# 2switch_LED_series.net
KiCad netlist of a schematic drawn in EAGLE
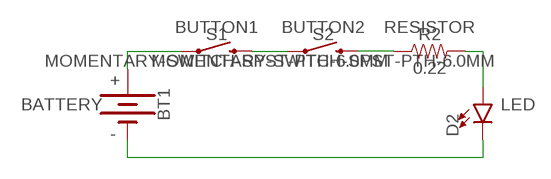
[diagram p0: schematic, sheet 1]

(export (version "E")
  (design (tool "Eeschema 10.0.6"))
  (components
    (comp (ref "BT1")
      (value "BATTERY-9V")
      (footprint "eagle-import:BATTCON_9V")
      (libsource (lib "eagle-import") (part "BATTERY-9V"))
    )
    (comp (ref "D2")
      (value "LED5MM")
      (footprint "eagle-import:LED_5MM")
      (libsource (lib "eagle-import") (part "LED5MM"))
    )
    (comp (ref "R2")
      (value "0.22")
      (footprint "eagle-import:0805")
      (libsource (lib "eagle-import") (part "0.22OHM-0805-1/4W-1%"))
    )
    (comp (ref "S1")
      (value "MOMENTARY-SWITCH-SPST-PTH-6.0MM")
      (footprint "eagle-import:TACTILE_SWITCH_PTH_6.0MM")
      (libsource (lib "eagle-import") (part "MOMENTARY-SWITCH-SPST-PTH-6.0MM"))
    )
    (comp (ref "S2")
      (value "MOMENTARY-SWITCH-SPST-PTH-6.0MM")
      (footprint "eagle-import:TACTILE_SWITCH_PTH_6.0MM")
      (libsource (lib "eagle-import") (part "MOMENTARY-SWITCH-SPST-PTH-6.0MM"))
    )
  )
  (nets
    (net (code "1") (name "Net-(BT1-Pad+)") (class "Default")
      (node (ref "BT1") (pin "+") (pinfunction "+_+") (pintype "power_in"))
      (node (ref "S1") (pin "1") (pinfunction "1_1") (pintype "passive"))
    )
    (net (code "2") (name "Net-(D2-C)") (class "Default")
      (node (ref "BT1") (pin "-") (pinfunction "-_-") (pintype "power_in"))
      (node (ref "D2") (pin "K") (pinfunction "C_K") (pintype "passive"))
    )
    (net (code "3") (name "Net-(D2-PadA)") (class "Default")
      (node (ref "D2") (pin "A") (pinfunction "A_A") (pintype "passive"))
      (node (ref "R2") (pin "2") (pinfunction "2_2") (pintype "passive"))
    )
    (net (code "4") (name "Net-(S1-2)") (class "Default")
      (node (ref "S1") (pin "3") (pinfunction "2_3") (pintype "passive"))
      (node (ref "S2") (pin "1") (pinfunction "1_1") (pintype "passive"))
    )
    (net (code "5") (name "Net-(S2-2)") (class "Default")
      (node (ref "R2") (pin "1") (pinfunction "1_1") (pintype "passive"))
      (node (ref "S2") (pin "3") (pinfunction "2_3") (pintype "passive"))
    )
  )
)
